# programmer.net
KiCad netlist of a schematic drawn in EAGLE
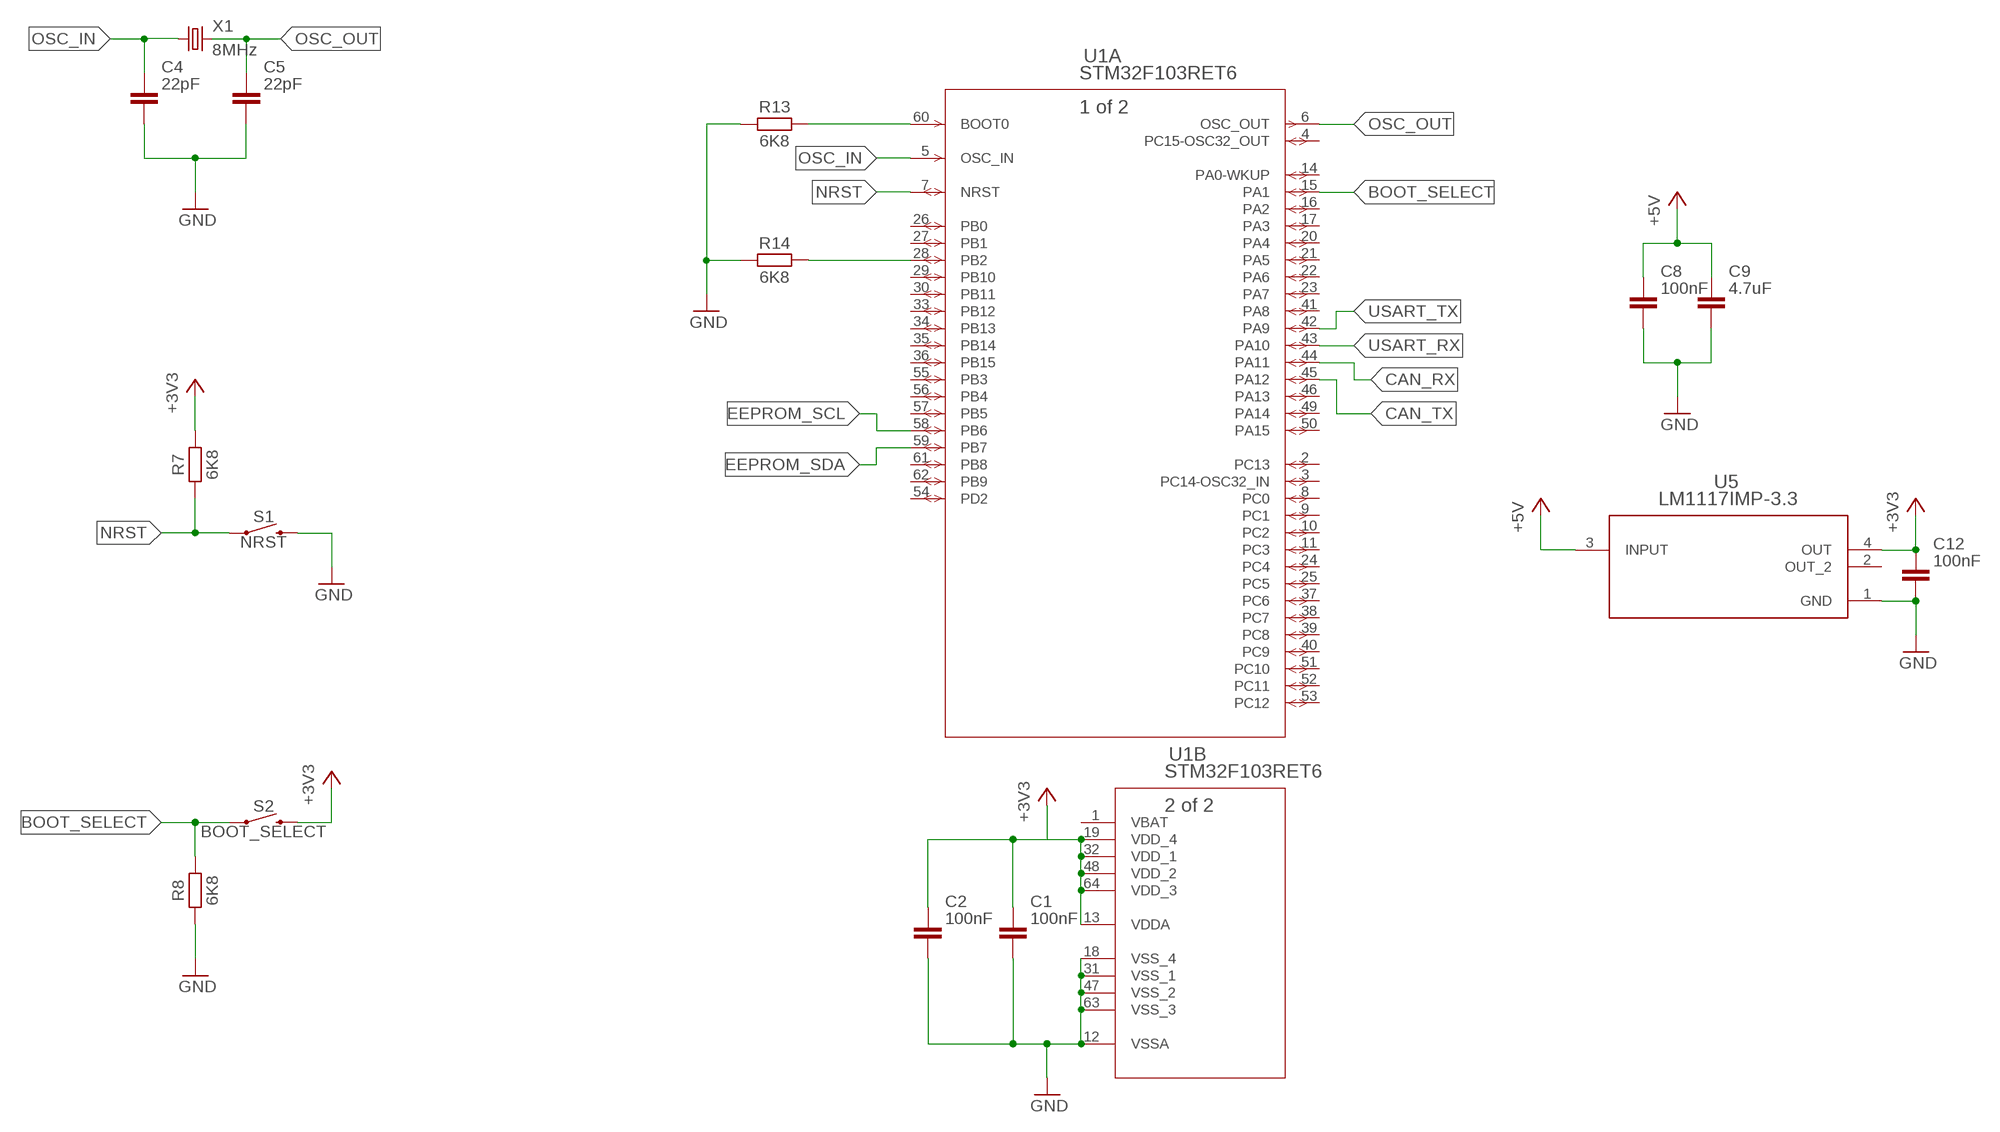
[diagram p0: schematic, sheet 1, part 1 of 2]
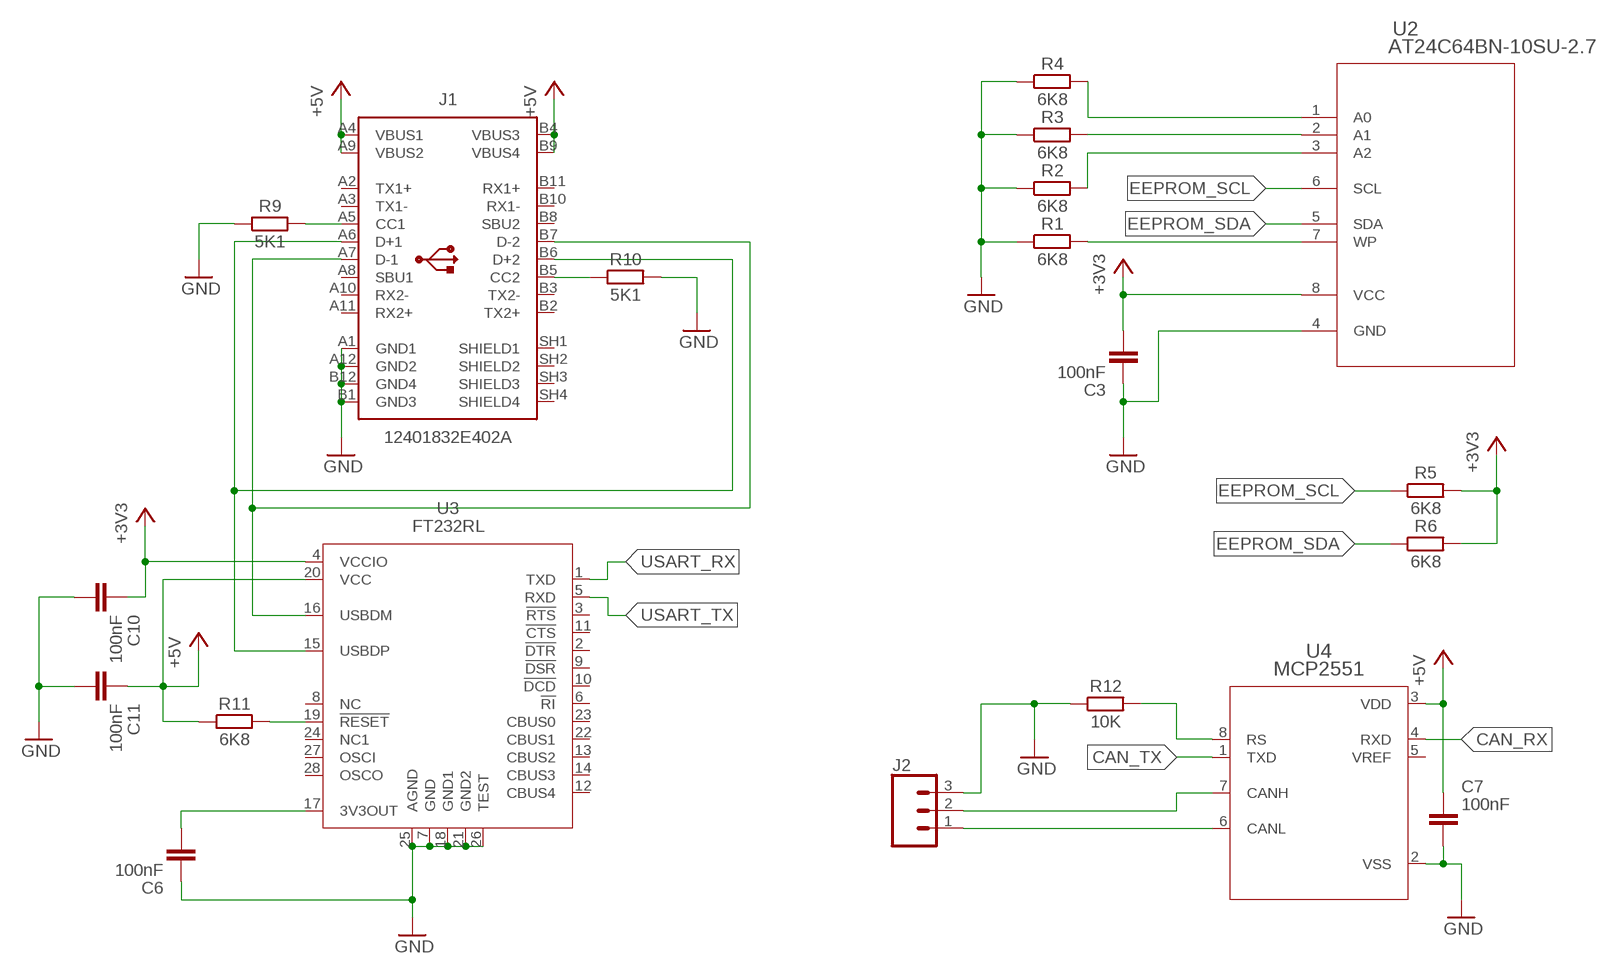
[diagram p1: schematic, sheet 1, part 2 of 2]

(export (version "E")
  (design (tool "Eeschema 10.0.6"))
  (components
    (comp (ref "C1")
      (value "100nF")
      (footprint "eagle-import:CAPC2012X110")
      (libsource (lib "eagle-import") (part "CCHIP-0805(2012-METRIC)_"))
    )
    (comp (ref "C2")
      (value "100nF")
      (footprint "eagle-import:CAPC2012X110")
      (libsource (lib "eagle-import") (part "CCHIP-0805(2012-METRIC)_"))
    )
    (comp (ref "C3")
      (value "100nF")
      (footprint "eagle-import:CAPC2012X110")
      (libsource (lib "eagle-import") (part "CCHIP-0805(2012-METRIC)_"))
    )
    (comp (ref "C4")
      (value "22pF")
      (footprint "eagle-import:CAPC2012X110")
      (libsource (lib "eagle-import") (part "CCHIP-0805(2012-METRIC)_"))
    )
    (comp (ref "C5")
      (value "22pF")
      (footprint "eagle-import:CAPC2012X110")
      (libsource (lib "eagle-import") (part "CCHIP-0805(2012-METRIC)_"))
    )
    (comp (ref "C6")
      (value "100nF")
      (footprint "eagle-import:CAPC2012X110")
      (libsource (lib "eagle-import") (part "CCHIP-0805(2012-METRIC)_"))
    )
    (comp (ref "C7")
      (value "100nF")
      (footprint "eagle-import:CAPC2012X110")
      (libsource (lib "eagle-import") (part "CCHIP-0805(2012-METRIC)_"))
    )
    (comp (ref "C8")
      (value "100nF")
      (footprint "eagle-import:CAPC2012X110")
      (libsource (lib "eagle-import") (part "CCHIP-0805(2012-METRIC)_"))
    )
    (comp (ref "C9")
      (value "4.7uF")
      (footprint "eagle-import:CAPC2012X110")
      (libsource (lib "eagle-import") (part "CCHIP-0805(2012-METRIC)_"))
    )
    (comp (ref "C10")
      (value "100nF")
      (footprint "eagle-import:CAPC2012X110")
      (libsource (lib "eagle-import") (part "CCHIP-0805(2012-METRIC)_"))
    )
    (comp (ref "C11")
      (value "100nF")
      (footprint "eagle-import:CAPC2012X110")
      (libsource (lib "eagle-import") (part "CCHIP-0805(2012-METRIC)_"))
    )
    (comp (ref "C12")
      (value "100nF")
      (footprint "eagle-import:CAPC2012X110")
      (libsource (lib "eagle-import") (part "CCHIP-0805(2012-METRIC)_"))
    )
    (comp (ref "J1")
      (value "12401832E402A")
      (footprint "eagle-import:12401832E402A")
      (fields (field (name "MANUFACTURER") "Amphenol ICC"))
      (libsource (lib "eagle-import") (part "12401832E402A"))
    )
    (comp (ref "J2")
      (value "CONN_03-SCREW-5MM")
      (footprint "eagle-import:SCREWTERMINAL-5MM-3")
      (libsource (lib "eagle-import") (part "CONN_03-SCREW-5MM"))
    )
    (comp (ref "R1")
      (value "6K8")
      (footprint "eagle-import:RESC2012X65")
      (libsource (lib "eagle-import") (part "RCHIP-0805(2012-METRIC)_"))
    )
    (comp (ref "R2")
      (value "6K8")
      (footprint "eagle-import:RESC2012X65")
      (libsource (lib "eagle-import") (part "RCHIP-0805(2012-METRIC)_"))
    )
    (comp (ref "R3")
      (value "6K8")
      (footprint "eagle-import:RESC2012X65")
      (libsource (lib "eagle-import") (part "RCHIP-0805(2012-METRIC)_"))
    )
    (comp (ref "R4")
      (value "6K8")
      (footprint "eagle-import:RESC2012X65")
      (libsource (lib "eagle-import") (part "RCHIP-0805(2012-METRIC)_"))
    )
    (comp (ref "R5")
      (value "6K8")
      (footprint "eagle-import:RESC2012X65")
      (libsource (lib "eagle-import") (part "RCHIP-0805(2012-METRIC)_"))
    )
    (comp (ref "R6")
      (value "6K8")
      (footprint "eagle-import:RESC2012X65")
      (libsource (lib "eagle-import") (part "RCHIP-0805(2012-METRIC)_"))
    )
    (comp (ref "R7")
      (value "6K8")
      (footprint "eagle-import:RESC2012X65")
      (libsource (lib "eagle-import") (part "RCHIP-0805(2012-METRIC)_"))
    )
    (comp (ref "R8")
      (value "6K8")
      (footprint "eagle-import:RESC2012X65")
      (libsource (lib "eagle-import") (part "RCHIP-0805(2012-METRIC)_"))
    )
    (comp (ref "R9")
      (value "5K1")
      (footprint "eagle-import:RESC2012X65")
      (libsource (lib "eagle-import") (part "RCHIP-0805(2012-METRIC)_"))
    )
    (comp (ref "R10")
      (value "5K1")
      (footprint "eagle-import:RESC2012X65")
      (libsource (lib "eagle-import") (part "RCHIP-0805(2012-METRIC)_"))
    )
    (comp (ref "R11")
      (value "6K8")
      (footprint "eagle-import:RESC2012X65")
      (libsource (lib "eagle-import") (part "RCHIP-0805(2012-METRIC)_"))
    )
    (comp (ref "R12")
      (value "10K")
      (footprint "eagle-import:RESC2012X65")
      (libsource (lib "eagle-import") (part "RCHIP-0805(2012-METRIC)_"))
    )
    (comp (ref "R13")
      (value "6K8")
      (footprint "eagle-import:RESC2012X65")
      (libsource (lib "eagle-import") (part "RCHIP-0805(2012-METRIC)_"))
    )
    (comp (ref "R14")
      (value "6K8")
      (footprint "eagle-import:RESC2012X65")
      (libsource (lib "eagle-import") (part "RCHIP-0805(2012-METRIC)_"))
    )
    (comp (ref "S1")
      (value "NRST")
      (footprint "eagle-import:TACTILE_SWITCH_SMD_6.0X3.5MM")
      (libsource (lib "eagle-import") (part "MOMENTARY-SWITCH-SPST-SMD-6.0X3.5MM"))
    )
    (comp (ref "S2")
      (value "BOOT_SELECT")
      (footprint "eagle-import:TACTILE_SWITCH_SMD_6.0X3.5MM")
      (libsource (lib "eagle-import") (part "MOMENTARY-SWITCH-SPST-SMD-6.0X3.5MM"))
    )
    (comp (ref "U1")
      (value "STM32F103RET6")
      (footprint "eagle-import:LQFP64-10X10MM")
      (fields (field (name "COPYRIGHT") "Copyright (C) 2018 Accelerated Designs. All rights reserved"))
      (libsource (lib "eagle-import") (part "STM32F103RET6"))
    )
    (comp (ref "U2")
      (value "AT24C64BN-10SU-2.7")
      (footprint "eagle-import:8S1_ATM")
      (libsource (lib "eagle-import") (part "AT24C64BN-10SU-2.7"))
    )
    (comp (ref "U3")
      (value "FT232RL")
      (footprint "eagle-import:SSOP28")
      (fields (field (name "MANUFACTURER") "FTDI Chip"))
      (libsource (lib "eagle-import") (part "FT232RL_SSOP"))
    )
    (comp (ref "U4")
      (value "MCP2551")
      (footprint "eagle-import:SOIC127P599X175-8")
      (fields (field (name "MANUFACTURER") "Microchip") (field (name "MPN") "MCP2551-E/SN"))
      (libsource (lib "eagle-import") (part "MCP2551_SOIC"))
    )
    (comp (ref "U5")
      (value "LM1117IMP-3.3")
      (footprint "eagle-import:DCY0004A_N")
      (fields
        (field (name "MANUFACTURER") "Texas Instruments")
        (field (name "PARTNUMBER") "LM1117IMP-3.3/NOPB")
      )
      (libsource (lib "eagle-import") (part "LM1117IMP-3.3/NOPB"))
    )
    (comp (ref "X1")
      (value "8MHz")
      (footprint "eagle-import:HC49-4-HSMX")
      (libsource (lib "eagle-import") (part "CRYSTALS-NOGND-4-HSMX"))
    )
  )
  (nets
    (net (code "1") (name "+3V3") (class "Default")
      (node (ref "C1") (pin "1") (pinfunction "1_1") (pintype "passive"))
      (node (ref "C10") (pin "1") (pinfunction "1_1") (pintype "passive"))
      (node (ref "C12") (pin "1") (pinfunction "1_1") (pintype "passive"))
      (node (ref "C2") (pin "1") (pinfunction "1_1") (pintype "passive"))
      (node (ref "C3") (pin "2") (pinfunction "2_2") (pintype "passive"))
      (node (ref "R5") (pin "2") (pinfunction "2_2") (pintype "passive"))
      (node (ref "R6") (pin "2") (pinfunction "2_2") (pintype "passive"))
      (node (ref "R7") (pin "2") (pinfunction "2_2") (pintype "passive"))
      (node (ref "S2") (pin "2") (pinfunction "2_2") (pintype "passive"))
      (node (ref "U1") (pin "13") (pinfunction "VDDA_13") (pintype "power_in"))
      (node (ref "U1") (pin "19") (pinfunction "VDD_4_19") (pintype "power_in"))
      (node (ref "U1") (pin "32") (pinfunction "VDD_1_32") (pintype "power_in"))
      (node (ref "U1") (pin "48") (pinfunction "VDD_2_48") (pintype "power_in"))
      (node (ref "U1") (pin "64") (pinfunction "VDD_3_64") (pintype "power_in"))
      (node (ref "U2") (pin "8") (pinfunction "VCC_8") (pintype "power_in"))
      (node (ref "U3") (pin "4") (pinfunction "VCCIO_4") (pintype "power_in"))
      (node (ref "U5") (pin "4") (pinfunction "OUT_4") (pintype "power_in"))
    )
    (net (code "2") (name "+5V") (class "Default")
      (node (ref "C11") (pin "1") (pinfunction "1_1") (pintype "passive"))
      (node (ref "C7") (pin "1") (pinfunction "1_1") (pintype "passive"))
      (node (ref "C8") (pin "1") (pinfunction "1_1") (pintype "passive"))
      (node (ref "C9") (pin "1") (pinfunction "1_1") (pintype "passive"))
      (node (ref "J1") (pin "A4") (pinfunction "VBUS1_A4") (pintype "power_in"))
      (node (ref "J1") (pin "A9") (pinfunction "VBUS2_A9") (pintype "power_in"))
      (node (ref "J1") (pin "B4") (pinfunction "VBUS3_B4") (pintype "power_in"))
      (node (ref "J1") (pin "B9") (pinfunction "VBUS4_B9") (pintype "power_in"))
      (node (ref "R11") (pin "1") (pinfunction "1_1") (pintype "passive"))
      (node (ref "U3") (pin "20") (pinfunction "VCC_20") (pintype "power_in"))
      (node (ref "U4") (pin "3") (pinfunction "VDD_3") (pintype "power_in"))
      (node (ref "U5") (pin "3") (pinfunction "INPUT_3") (pintype "power_in"))
    )
    (net (code "3") (name "/OUT_2") (class "Default")
      (node (ref "U5") (pin "2") (pinfunction "OUT_2_2") (pintype "power_in"))
    )
    (net (code "4") (name "/SHIELD1") (class "Default")
      (node (ref "J1") (pin "SH1") (pinfunction "SHIELD1_SH1") (pintype "power_in"))
    )
    (net (code "5") (name "/SHIELD2") (class "Default")
      (node (ref "J1") (pin "SH2") (pinfunction "SHIELD2_SH2") (pintype "power_in"))
    )
    (net (code "6") (name "/SHIELD3") (class "Default")
      (node (ref "J1") (pin "SH3") (pinfunction "SHIELD3_SH3") (pintype "power_in"))
    )
    (net (code "7") (name "/SHIELD4") (class "Default")
      (node (ref "J1") (pin "SH4") (pinfunction "SHIELD4_SH4") (pintype "power_in"))
    )
    (net (code "8") (name "/VBAT") (class "Default")
      (node (ref "U1") (pin "1") (pinfunction "VBAT_1") (pintype "power_in"))
    )
    (net (code "9") (name "BOOT_SELECT") (class "Default")
      (node (ref "R8") (pin "2") (pinfunction "2_2") (pintype "passive"))
      (node (ref "S2") (pin "1") (pinfunction "1_1") (pintype "passive"))
      (node (ref "U1") (pin "15") (pinfunction "PA1_15") (pintype "bidirectional"))
    )
    (net (code "10") (name "CAN_RX") (class "Default")
      (node (ref "U1") (pin "44") (pinfunction "PA11_44") (pintype "bidirectional"))
      (node (ref "U4") (pin "4") (pinfunction "RXD_4") (pintype "output"))
    )
    (net (code "11") (name "CAN_TX") (class "Default")
      (node (ref "U1") (pin "45") (pinfunction "PA12_45") (pintype "bidirectional"))
      (node (ref "U4") (pin "1") (pinfunction "TXD_1") (pintype "input"))
    )
    (net (code "12") (name "EEPROM_SCL") (class "Default")
      (node (ref "R5") (pin "1") (pinfunction "1_1") (pintype "passive"))
      (node (ref "U1") (pin "58") (pinfunction "PB6_58") (pintype "bidirectional"))
      (node (ref "U2") (pin "6") (pinfunction "SCL_6") (pintype "input"))
    )
    (net (code "13") (name "EEPROM_SDA") (class "Default")
      (node (ref "R6") (pin "1") (pinfunction "1_1") (pintype "passive"))
      (node (ref "U1") (pin "59") (pinfunction "PB7_59") (pintype "bidirectional"))
      (node (ref "U2") (pin "5") (pinfunction "SDA_5") (pintype "passive"))
    )
    (net (code "14") (name "GND") (class "Default")
      (node (ref "C1") (pin "2") (pinfunction "2_2") (pintype "passive"))
      (node (ref "C10") (pin "2") (pinfunction "2_2") (pintype "passive"))
      (node (ref "C11") (pin "2") (pinfunction "2_2") (pintype "passive"))
      (node (ref "C12") (pin "2") (pinfunction "2_2") (pintype "passive"))
      (node (ref "C2") (pin "2") (pinfunction "2_2") (pintype "passive"))
      (node (ref "C3") (pin "1") (pinfunction "1_1") (pintype "passive"))
      (node (ref "C4") (pin "2") (pinfunction "2_2") (pintype "passive"))
      (node (ref "C5") (pin "2") (pinfunction "2_2") (pintype "passive"))
      (node (ref "C6") (pin "1") (pinfunction "1_1") (pintype "passive"))
      (node (ref "C7") (pin "2") (pinfunction "2_2") (pintype "passive"))
      (node (ref "C8") (pin "2") (pinfunction "2_2") (pintype "passive"))
      (node (ref "C9") (pin "2") (pinfunction "2_2") (pintype "passive"))
      (node (ref "J1") (pin "A1") (pinfunction "GND1_A1") (pintype "power_in"))
      (node (ref "J1") (pin "A12") (pinfunction "GND2_A12") (pintype "power_in"))
      (node (ref "J1") (pin "B1") (pinfunction "GND3_B1") (pintype "power_in"))
      (node (ref "J1") (pin "B12") (pinfunction "GND4_B12") (pintype "power_in"))
      (node (ref "J2") (pin "3") (pinfunction "3_3") (pintype "passive"))
      (node (ref "R1") (pin "1") (pinfunction "1_1") (pintype "passive"))
      (node (ref "R10") (pin "2") (pinfunction "2_2") (pintype "passive"))
      (node (ref "R12") (pin "1") (pinfunction "1_1") (pintype "passive"))
      (node (ref "R13") (pin "1") (pinfunction "1_1") (pintype "passive"))
      (node (ref "R14") (pin "1") (pinfunction "1_1") (pintype "passive"))
      (node (ref "R2") (pin "1") (pinfunction "1_1") (pintype "passive"))
      (node (ref "R3") (pin "1") (pinfunction "1_1") (pintype "passive"))
      (node (ref "R4") (pin "1") (pinfunction "1_1") (pintype "passive"))
      (node (ref "R8") (pin "1") (pinfunction "1_1") (pintype "passive"))
      (node (ref "R9") (pin "1") (pinfunction "1_1") (pintype "passive"))
      (node (ref "S1") (pin "2") (pinfunction "2_2") (pintype "passive"))
      (node (ref "U1") (pin "12") (pinfunction "VSSA_12") (pintype "power_in"))
      (node (ref "U1") (pin "18") (pinfunction "VSS_4_18") (pintype "power_in"))
      (node (ref "U1") (pin "31") (pinfunction "VSS_1_31") (pintype "power_in"))
      (node (ref "U1") (pin "47") (pinfunction "VSS_2_47") (pintype "power_in"))
      (node (ref "U1") (pin "63") (pinfunction "VSS_3_63") (pintype "power_in"))
      (node (ref "U2") (pin "4") (pinfunction "GND_4") (pintype "power_in"))
      (node (ref "U3") (pin "18") (pinfunction "GND1_18") (pintype "power_in"))
      (node (ref "U3") (pin "21") (pinfunction "GND2_21") (pintype "power_in"))
      (node (ref "U3") (pin "25") (pinfunction "AGND_25") (pintype "power_in"))
      (node (ref "U3") (pin "26") (pinfunction "TEST_26") (pintype "input"))
      (node (ref "U3") (pin "7") (pinfunction "GND_7") (pintype "power_in"))
      (node (ref "U4") (pin "2") (pinfunction "VSS_2") (pintype "power_in"))
      (node (ref "U5") (pin "1") (pinfunction "GND_1") (pintype "power_in"))
    )
    (net (code "15") (name "NRST") (class "Default")
      (node (ref "R7") (pin "1") (pinfunction "1_1") (pintype "passive"))
      (node (ref "S1") (pin "1") (pinfunction "1_1") (pintype "passive"))
      (node (ref "U1") (pin "7") (pinfunction "NRST_7") (pintype "bidirectional"))
    )
    (net (code "16") (name "Net-(J1-CC1)") (class "Default")
      (node (ref "J1") (pin "A5") (pinfunction "CC1_A5") (pintype "bidirectional"))
      (node (ref "R9") (pin "2") (pinfunction "2_2") (pintype "passive"))
    )
    (net (code "17") (name "Net-(J1-CC2)") (class "Default")
      (node (ref "J1") (pin "B5") (pinfunction "CC2_B5") (pintype "bidirectional"))
      (node (ref "R10") (pin "1") (pinfunction "1_1") (pintype "passive"))
    )
    (net (code "18") (name "Net-(J1-D+1)") (class "Default")
      (node (ref "J1") (pin "A6") (pinfunction "D+1_A6") (pintype "bidirectional"))
      (node (ref "J1") (pin "B6") (pinfunction "D+2_B6") (pintype "bidirectional"))
      (node (ref "U3") (pin "15") (pinfunction "USBDP_15") (pintype "bidirectional"))
    )
    (net (code "19") (name "Net-(J1-D-1)") (class "Default")
      (node (ref "J1") (pin "A7") (pinfunction "D-1_A7") (pintype "bidirectional"))
      (node (ref "J1") (pin "B7") (pinfunction "D-2_B7") (pintype "bidirectional"))
      (node (ref "U3") (pin "16") (pinfunction "USBDM_16") (pintype "bidirectional"))
    )
    (net (code "20") (name "Net-(U1A-BOOT0)") (class "Default")
      (node (ref "R13") (pin "2") (pinfunction "2_2") (pintype "passive"))
      (node (ref "U1") (pin "60") (pinfunction "BOOT0_60") (pintype "input"))
    )
    (net (code "21") (name "Net-(U1A-PB2)") (class "Default")
      (node (ref "R14") (pin "2") (pinfunction "2_2") (pintype "passive"))
      (node (ref "U1") (pin "28") (pinfunction "PB2_28") (pintype "bidirectional"))
    )
    (net (code "22") (name "Net-(U2-A0)") (class "Default")
      (node (ref "R4") (pin "2") (pinfunction "2_2") (pintype "passive"))
      (node (ref "U2") (pin "1") (pinfunction "A0_1") (pintype "input"))
    )
    (net (code "23") (name "Net-(U2-A1)") (class "Default")
      (node (ref "R3") (pin "2") (pinfunction "2_2") (pintype "passive"))
      (node (ref "U2") (pin "2") (pinfunction "A1_2") (pintype "input"))
    )
    (net (code "24") (name "Net-(U2-A2)") (class "Default")
      (node (ref "R2") (pin "2") (pinfunction "2_2") (pintype "passive"))
      (node (ref "U2") (pin "3") (pinfunction "A2_3") (pintype "input"))
    )
    (net (code "25") (name "Net-(U2-WP)") (class "Default")
      (node (ref "R1") (pin "2") (pinfunction "2_2") (pintype "passive"))
      (node (ref "U2") (pin "7") (pinfunction "WP_7") (pintype "passive"))
    )
    (net (code "26") (name "Net-(U3-3V3OUT)") (class "Default")
      (node (ref "C6") (pin "2") (pinfunction "2_2") (pintype "passive"))
      (node (ref "U3") (pin "17") (pinfunction "3V3OUT_17") (pintype "output"))
    )
    (net (code "27") (name "Net-(U3-~{RESET})") (class "Default")
      (node (ref "R11") (pin "2") (pinfunction "2_2") (pintype "passive"))
      (node (ref "U3") (pin "19") (pinfunction "~{RESET}_19") (pintype "input"))
    )
    (net (code "28") (name "Net-(U4-CANH)") (class "Default")
      (node (ref "J2") (pin "2") (pinfunction "2_2") (pintype "passive"))
      (node (ref "U4") (pin "7") (pinfunction "CANH_7") (pintype "bidirectional"))
    )
    (net (code "29") (name "Net-(U4-CANL)") (class "Default")
      (node (ref "J2") (pin "1") (pinfunction "1_1") (pintype "passive"))
      (node (ref "U4") (pin "6") (pinfunction "CANL_6") (pintype "bidirectional"))
    )
    (net (code "30") (name "Net-(U4-RS)") (class "Default")
      (node (ref "R12") (pin "2") (pinfunction "2_2") (pintype "passive"))
      (node (ref "U4") (pin "8") (pinfunction "RS_8") (pintype "input"))
    )
    (net (code "31") (name "OSC_IN") (class "Default")
      (node (ref "C4") (pin "1") (pinfunction "1_1") (pintype "passive"))
      (node (ref "U1") (pin "5") (pinfunction "OSC_IN_5") (pintype "input"))
      (node (ref "X1") (pin "1") (pinfunction "1_1") (pintype "passive"))
    )
    (net (code "32") (name "OSC_OUT") (class "Default")
      (node (ref "C5") (pin "1") (pinfunction "1_1") (pintype "passive"))
      (node (ref "U1") (pin "6") (pinfunction "OSC_OUT_6") (pintype "output"))
      (node (ref "X1") (pin "2") (pinfunction "2_2") (pintype "passive"))
    )
    (net (code "33") (name "USART_RX") (class "Default")
      (node (ref "U1") (pin "43") (pinfunction "PA10_43") (pintype "bidirectional"))
      (node (ref "U3") (pin "1") (pinfunction "TXD_1") (pintype "output"))
    )
    (net (code "34") (name "USART_TX") (class "Default")
      (node (ref "U1") (pin "42") (pinfunction "PA9_42") (pintype "bidirectional"))
      (node (ref "U3") (pin "5") (pinfunction "RXD_5") (pintype "input"))
    )
    (net (code "35") (name "unconnected-(J1-RX1+-PadB11)") (class "Default")
      (node (ref "J1") (pin "B11") (pinfunction "RX1+_B11") (pintype "bidirectional"))
    )
    (net (code "36") (name "unconnected-(J1-RX1--PadB10)") (class "Default")
      (node (ref "J1") (pin "B10") (pinfunction "RX1-_B10") (pintype "bidirectional"))
    )
    (net (code "37") (name "unconnected-(J1-RX2+-PadA11)") (class "Default")
      (node (ref "J1") (pin "A11") (pinfunction "RX2+_A11") (pintype "bidirectional"))
    )
    (net (code "38") (name "unconnected-(J1-RX2--PadA10)") (class "Default")
      (node (ref "J1") (pin "A10") (pinfunction "RX2-_A10") (pintype "bidirectional"))
    )
    (net (code "39") (name "unconnected-(J1-SBU1-PadA8)") (class "Default")
      (node (ref "J1") (pin "A8") (pinfunction "SBU1_A8") (pintype "bidirectional"))
    )
    (net (code "40") (name "unconnected-(J1-SBU2-PadB8)") (class "Default")
      (node (ref "J1") (pin "B8") (pinfunction "SBU2_B8") (pintype "bidirectional"))
    )
    (net (code "41") (name "unconnected-(J1-TX1+-PadA2)") (class "Default")
      (node (ref "J1") (pin "A2") (pinfunction "TX1+_A2") (pintype "bidirectional"))
    )
    (net (code "42") (name "unconnected-(J1-TX1--PadA3)") (class "Default")
      (node (ref "J1") (pin "A3") (pinfunction "TX1-_A3") (pintype "bidirectional"))
    )
    (net (code "43") (name "unconnected-(J1-TX2+-PadB2)") (class "Default")
      (node (ref "J1") (pin "B2") (pinfunction "TX2+_B2") (pintype "bidirectional"))
    )
    (net (code "44") (name "unconnected-(J1-TX2--PadB3)") (class "Default")
      (node (ref "J1") (pin "B3") (pinfunction "TX2-_B3") (pintype "bidirectional"))
    )
    (net (code "45") (name "unconnected-(U1A-PA0-WKUP-Pad14)") (class "Default")
      (node (ref "U1") (pin "14") (pinfunction "PA0-WKUP_14") (pintype "bidirectional"))
    )
    (net (code "46") (name "unconnected-(U1A-PA2-Pad16)") (class "Default")
      (node (ref "U1") (pin "16") (pinfunction "PA2_16") (pintype "bidirectional"))
    )
    (net (code "47") (name "unconnected-(U1A-PA3-Pad17)") (class "Default")
      (node (ref "U1") (pin "17") (pinfunction "PA3_17") (pintype "bidirectional"))
    )
    (net (code "48") (name "unconnected-(U1A-PA4-Pad20)") (class "Default")
      (node (ref "U1") (pin "20") (pinfunction "PA4_20") (pintype "bidirectional"))
    )
    (net (code "49") (name "unconnected-(U1A-PA5-Pad21)") (class "Default")
      (node (ref "U1") (pin "21") (pinfunction "PA5_21") (pintype "bidirectional"))
    )
    (net (code "50") (name "unconnected-(U1A-PA6-Pad22)") (class "Default")
      (node (ref "U1") (pin "22") (pinfunction "PA6_22") (pintype "bidirectional"))
    )
    (net (code "51") (name "unconnected-(U1A-PA7-Pad23)") (class "Default")
      (node (ref "U1") (pin "23") (pinfunction "PA7_23") (pintype "bidirectional"))
    )
    (net (code "52") (name "unconnected-(U1A-PA8-Pad41)") (class "Default")
      (node (ref "U1") (pin "41") (pinfunction "PA8_41") (pintype "bidirectional"))
    )
    (net (code "53") (name "unconnected-(U1A-PA13-Pad46)") (class "Default")
      (node (ref "U1") (pin "46") (pinfunction "PA13_46") (pintype "bidirectional"))
    )
    (net (code "54") (name "unconnected-(U1A-PA14-Pad49)") (class "Default")
      (node (ref "U1") (pin "49") (pinfunction "PA14_49") (pintype "bidirectional"))
    )
    (net (code "55") (name "unconnected-(U1A-PA15-Pad50)") (class "Default")
      (node (ref "U1") (pin "50") (pinfunction "PA15_50") (pintype "bidirectional"))
    )
    (net (code "56") (name "unconnected-(U1A-PB0-Pad26)") (class "Default")
      (node (ref "U1") (pin "26") (pinfunction "PB0_26") (pintype "bidirectional"))
    )
    (net (code "57") (name "unconnected-(U1A-PB1-Pad27)") (class "Default")
      (node (ref "U1") (pin "27") (pinfunction "PB1_27") (pintype "bidirectional"))
    )
    (net (code "58") (name "unconnected-(U1A-PB3-Pad55)") (class "Default")
      (node (ref "U1") (pin "55") (pinfunction "PB3_55") (pintype "bidirectional"))
    )
    (net (code "59") (name "unconnected-(U1A-PB4-Pad56)") (class "Default")
      (node (ref "U1") (pin "56") (pinfunction "PB4_56") (pintype "bidirectional"))
    )
    (net (code "60") (name "unconnected-(U1A-PB5-Pad57)") (class "Default")
      (node (ref "U1") (pin "57") (pinfunction "PB5_57") (pintype "bidirectional"))
    )
    (net (code "61") (name "unconnected-(U1A-PB8-Pad61)") (class "Default")
      (node (ref "U1") (pin "61") (pinfunction "PB8_61") (pintype "bidirectional"))
    )
    (net (code "62") (name "unconnected-(U1A-PB9-Pad62)") (class "Default")
      (node (ref "U1") (pin "62") (pinfunction "PB9_62") (pintype "bidirectional"))
    )
    (net (code "63") (name "unconnected-(U1A-PB10-Pad29)") (class "Default")
      (node (ref "U1") (pin "29") (pinfunction "PB10_29") (pintype "bidirectional"))
    )
    (net (code "64") (name "unconnected-(U1A-PB11-Pad30)") (class "Default")
      (node (ref "U1") (pin "30") (pinfunction "PB11_30") (pintype "bidirectional"))
    )
    (net (code "65") (name "unconnected-(U1A-PB12-Pad33)") (class "Default")
      (node (ref "U1") (pin "33") (pinfunction "PB12_33") (pintype "bidirectional"))
    )
    (net (code "66") (name "unconnected-(U1A-PB13-Pad34)") (class "Default")
      (node (ref "U1") (pin "34") (pinfunction "PB13_34") (pintype "bidirectional"))
    )
    (net (code "67") (name "unconnected-(U1A-PB14-Pad35)") (class "Default")
      (node (ref "U1") (pin "35") (pinfunction "PB14_35") (pintype "bidirectional"))
    )
    (net (code "68") (name "unconnected-(U1A-PB15-Pad36)") (class "Default")
      (node (ref "U1") (pin "36") (pinfunction "PB15_36") (pintype "bidirectional"))
    )
    (net (code "69") (name "unconnected-(U1A-PC0-Pad8)") (class "Default")
      (node (ref "U1") (pin "8") (pinfunction "PC0_8") (pintype "bidirectional"))
    )
    (net (code "70") (name "unconnected-(U1A-PC1-Pad9)") (class "Default")
      (node (ref "U1") (pin "9") (pinfunction "PC1_9") (pintype "bidirectional"))
    )
    (net (code "71") (name "unconnected-(U1A-PC2-Pad10)") (class "Default")
      (node (ref "U1") (pin "10") (pinfunction "PC2_10") (pintype "bidirectional"))
    )
    (net (code "72") (name "unconnected-(U1A-PC3-Pad11)") (class "Default")
      (node (ref "U1") (pin "11") (pinfunction "PC3_11") (pintype "bidirectional"))
    )
    (net (code "73") (name "unconnected-(U1A-PC4-Pad24)") (class "Default")
      (node (ref "U1") (pin "24") (pinfunction "PC4_24") (pintype "bidirectional"))
    )
    (net (code "74") (name "unconnected-(U1A-PC5-Pad25)") (class "Default")
      (node (ref "U1") (pin "25") (pinfunction "PC5_25") (pintype "bidirectional"))
    )
    (net (code "75") (name "unconnected-(U1A-PC6-Pad37)") (class "Default")
      (node (ref "U1") (pin "37") (pinfunction "PC6_37") (pintype "bidirectional"))
    )
    (net (code "76") (name "unconnected-(U1A-PC7-Pad38)") (class "Default")
      (node (ref "U1") (pin "38") (pinfunction "PC7_38") (pintype "bidirectional"))
    )
    (net (code "77") (name "unconnected-(U1A-PC8-Pad39)") (class "Default")
      (node (ref "U1") (pin "39") (pinfunction "PC8_39") (pintype "bidirectional"))
    )
    (net (code "78") (name "unconnected-(U1A-PC9-Pad40)") (class "Default")
      (node (ref "U1") (pin "40") (pinfunction "PC9_40") (pintype "bidirectional"))
    )
    (net (code "79") (name "unconnected-(U1A-PC10-Pad51)") (class "Default")
      (node (ref "U1") (pin "51") (pinfunction "PC10_51") (pintype "bidirectional"))
    )
    (net (code "80") (name "unconnected-(U1A-PC11-Pad52)") (class "Default")
      (node (ref "U1") (pin "52") (pinfunction "PC11_52") (pintype "bidirectional"))
    )
    (net (code "81") (name "unconnected-(U1A-PC12-Pad53)") (class "Default")
      (node (ref "U1") (pin "53") (pinfunction "PC12_53") (pintype "bidirectional"))
    )
    (net (code "82") (name "unconnected-(U1A-PC13-Pad2)") (class "Default")
      (node (ref "U1") (pin "2") (pinfunction "PC13_2") (pintype "bidirectional"))
    )
    (net (code "83") (name "unconnected-(U1A-PC14-OSC32_IN-Pad3)") (class "Default")
      (node (ref "U1") (pin "3") (pinfunction "PC14-OSC32_IN_3") (pintype "bidirectional"))
    )
    (net (code "84") (name "unconnected-(U1A-PC15-OSC32_OUT-Pad4)") (class "Default")
      (node (ref "U1") (pin "4") (pinfunction "PC15-OSC32_OUT_4") (pintype "bidirectional"))
    )
    (net (code "85") (name "unconnected-(U1A-PD2-Pad54)") (class "Default")
      (node (ref "U1") (pin "54") (pinfunction "PD2_54") (pintype "bidirectional"))
    )
    (net (code "86") (name "unconnected-(U3-CBUS0-Pad23)") (class "Default")
      (node (ref "U3") (pin "23") (pinfunction "CBUS0_23") (pintype "bidirectional"))
    )
    (net (code "87") (name "unconnected-(U3-CBUS1-Pad22)") (class "Default")
      (node (ref "U3") (pin "22") (pinfunction "CBUS1_22") (pintype "bidirectional"))
    )
    (net (code "88") (name "unconnected-(U3-CBUS2-Pad13)") (class "Default")
      (node (ref "U3") (pin "13") (pinfunction "CBUS2_13") (pintype "bidirectional"))
    )
    (net (code "89") (name "unconnected-(U3-CBUS3-Pad14)") (class "Default")
      (node (ref "U3") (pin "14") (pinfunction "CBUS3_14") (pintype "bidirectional"))
    )
    (net (code "90") (name "unconnected-(U3-CBUS4-Pad12)") (class "Default")
      (node (ref "U3") (pin "12") (pinfunction "CBUS4_12") (pintype "bidirectional"))
    )
    (net (code "91") (name "unconnected-(U3-NC-Pad8)") (class "Default")
      (node (ref "U3") (pin "8") (pinfunction "NC_8") (pintype "no_connect"))
    )
    (net (code "92") (name "unconnected-(U3-NC1-Pad24)") (class "Default")
      (node (ref "U3") (pin "24") (pinfunction "NC1_24") (pintype "no_connect"))
    )
    (net (code "93") (name "unconnected-(U3-OSCI-Pad27)") (class "Default")
      (node (ref "U3") (pin "27") (pinfunction "OSCI_27") (pintype "input"))
    )
    (net (code "94") (name "unconnected-(U3-OSCO-Pad28)") (class "Default")
      (node (ref "U3") (pin "28") (pinfunction "OSCO_28") (pintype "input"))
    )
    (net (code "95") (name "unconnected-(U3-~{CTS}-Pad11)") (class "Default")
      (node (ref "U3") (pin "11") (pinfunction "~{CTS}_11") (pintype "input"))
    )
    (net (code "96") (name "unconnected-(U3-~{DCD}-Pad10)") (class "Default")
      (node (ref "U3") (pin "10") (pinfunction "~{DCD}_10") (pintype "input"))
    )
    (net (code "97") (name "unconnected-(U3-~{DSR}-Pad9)") (class "Default")
      (node (ref "U3") (pin "9") (pinfunction "~{DSR}_9") (pintype "input"))
    )
    (net (code "98") (name "unconnected-(U3-~{DTR}-Pad2)") (class "Default")
      (node (ref "U3") (pin "2") (pinfunction "~{DTR}_2") (pintype "output"))
    )
    (net (code "99") (name "unconnected-(U3-~{RI}-Pad6)") (class "Default")
      (node (ref "U3") (pin "6") (pinfunction "~{RI}_6") (pintype "input"))
    )
    (net (code "100") (name "unconnected-(U3-~{RTS}-Pad3)") (class "Default")
      (node (ref "U3") (pin "3") (pinfunction "~{RTS}_3") (pintype "output"))
    )
    (net (code "101") (name "unconnected-(U4-VREF-Pad5)") (class "Default")
      (node (ref "U4") (pin "5") (pinfunction "VREF_5") (pintype "output"))
    )
  )
)
